# MCU.net
KiCad netlist of a schematic drawn in Altium Designer
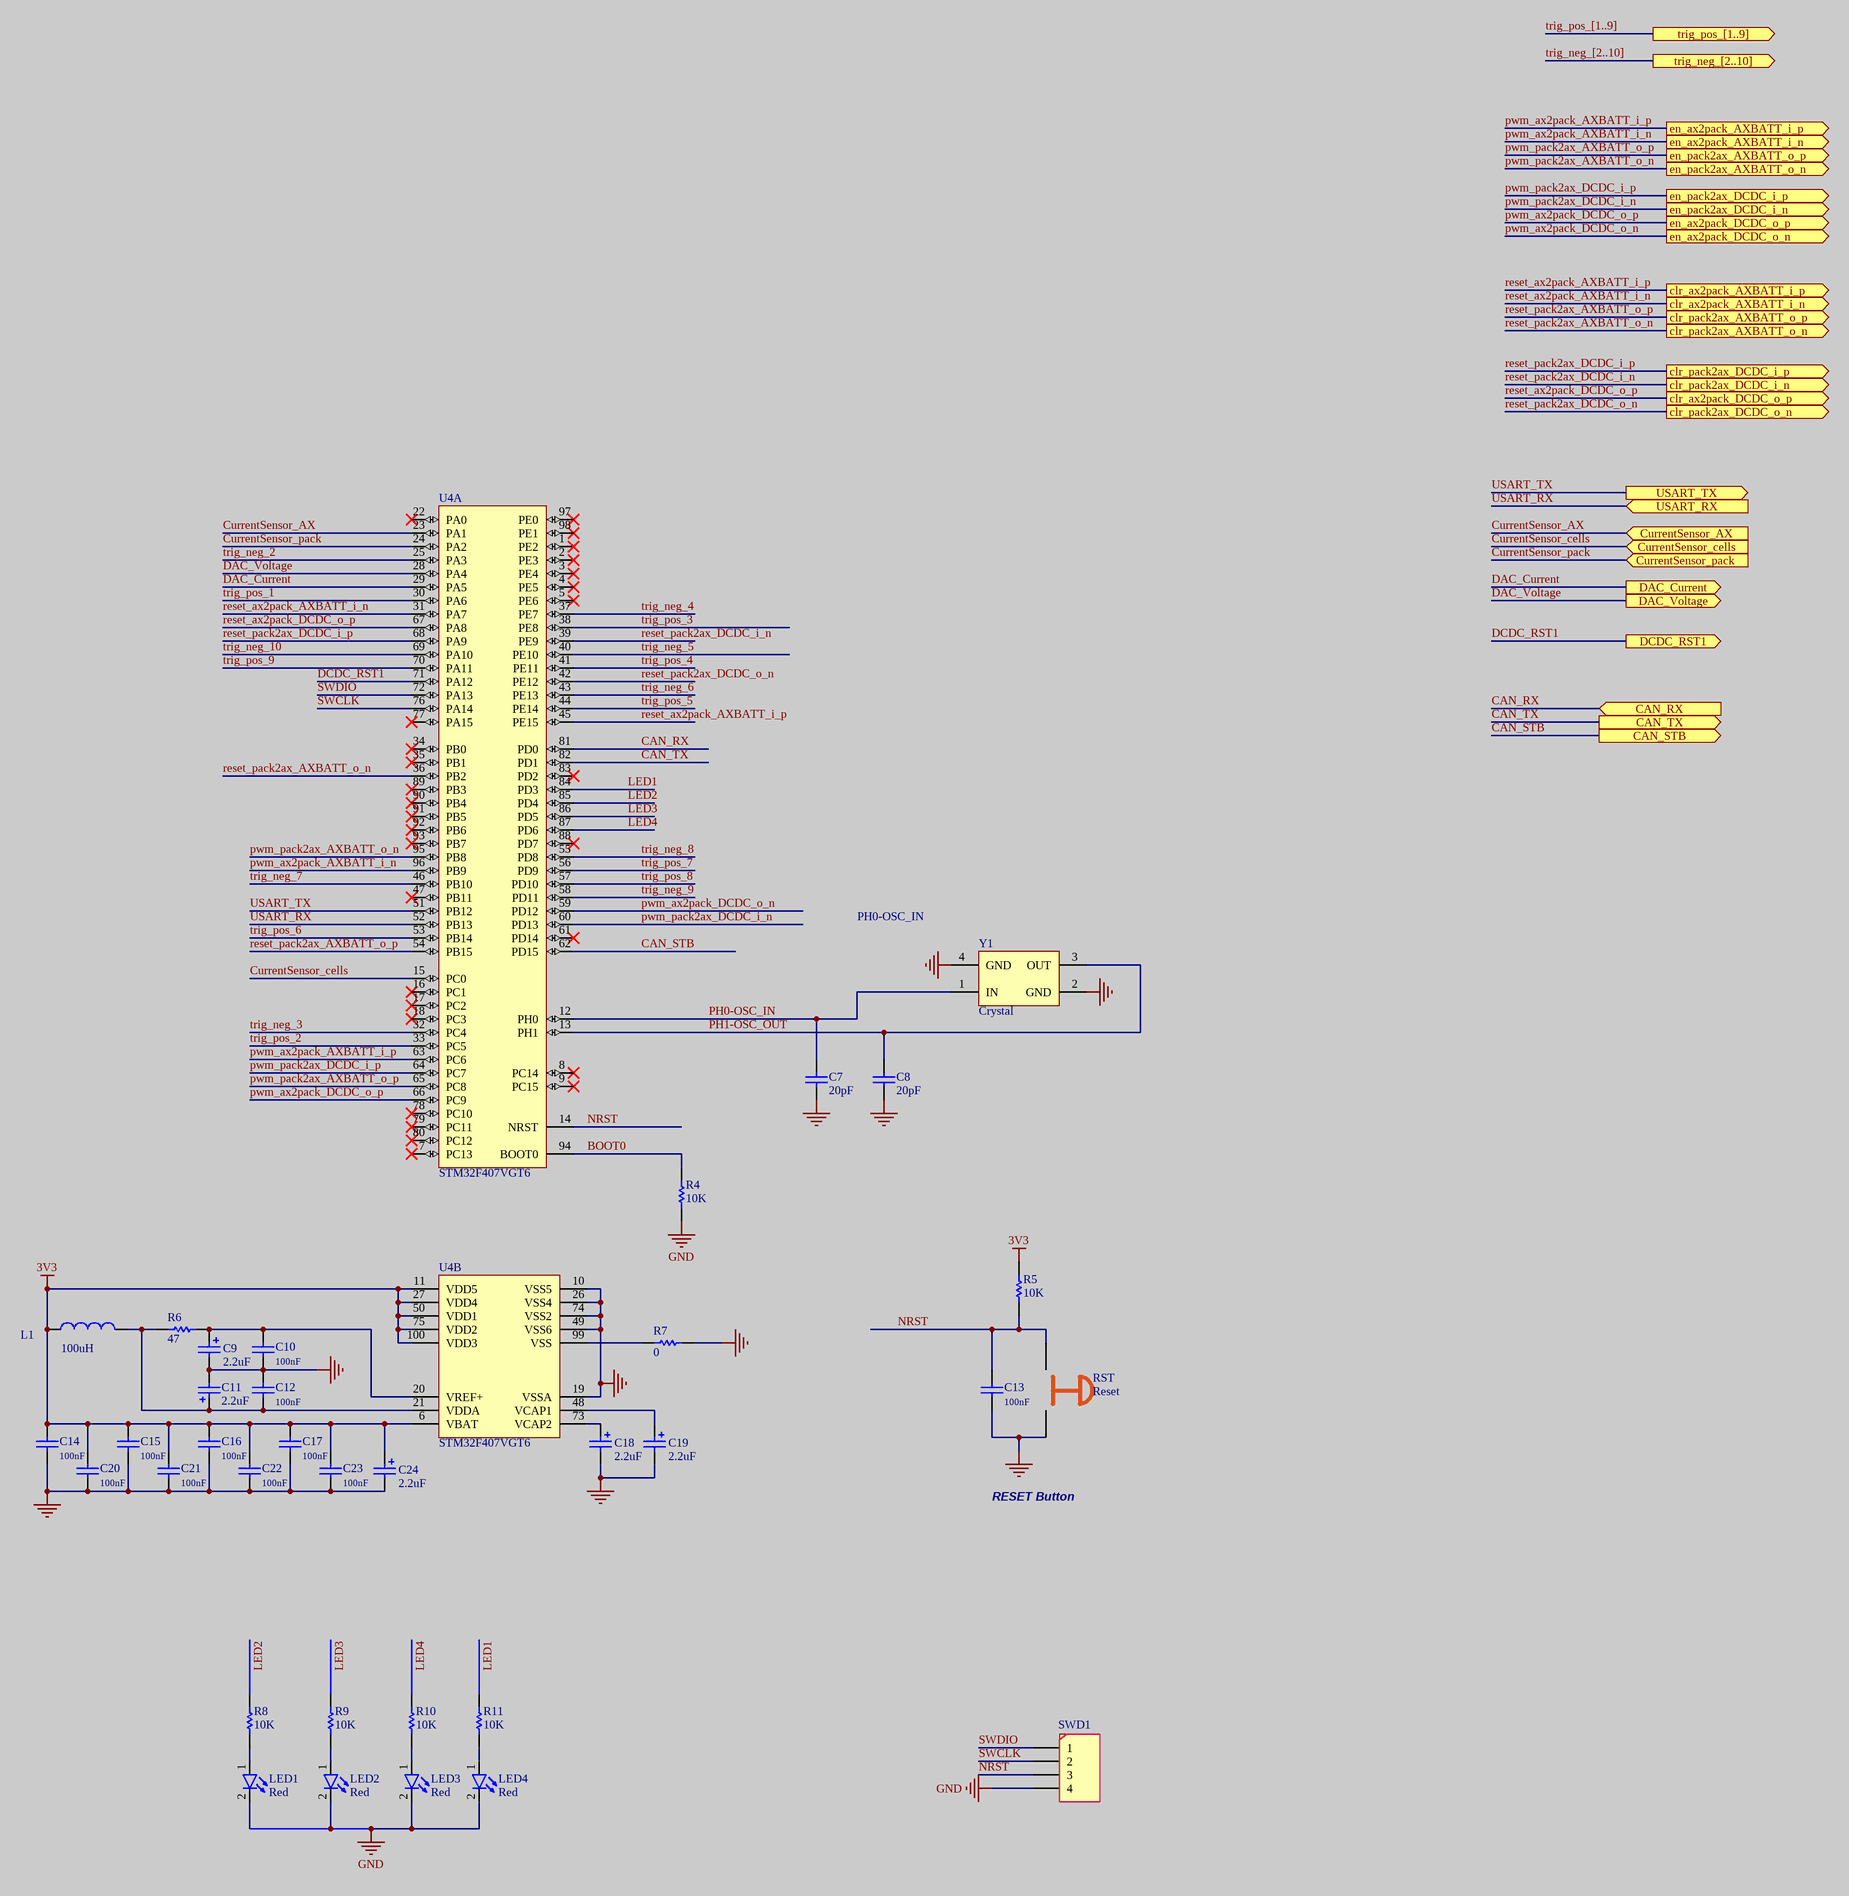
[diagram p0: MCU.SchDoc]

(export (version "E")
  (design (tool "Eeschema 10.0.6"))
  (components
    (comp (ref "C7")
      (value "20pF")
      (footprint "CAPC0603")
      (description "Capacitor")
      (fields (field (name "PUBLISHER") "Altium Limited"))
      (libsource (lib "eLIB") (part "Capacitor"))
    )
    (comp (ref "C8")
      (value "20pF")
      (footprint "CAPC0603")
      (description "Capacitor")
      (fields (field (name "PUBLISHER") "Altium Limited"))
      (libsource (lib "eLIB") (part "Capacitor"))
    )
    (comp (ref "C9")
      (value "2.2uF")
      (footprint "C1206")
      (description "Tantalium Capacitor Size C")
      (fields (field (name "PUBLISHER") "Altium Limited"))
      (libsource (lib "eLIB") (part "Cap_Tan"))
    )
    (comp (ref "C10")
      (value "100nF")
      (footprint "CAPC0603")
      (description "Capacitor")
      (fields (field (name "PUBLISHER") "Altium Limited"))
      (libsource (lib "eLIB") (part "Capacitor"))
    )
    (comp (ref "C11")
      (value "2.2uF")
      (footprint "C1206")
      (description "Tantalium Capacitor Size C")
      (fields (field (name "PUBLISHER") "Altium Limited"))
      (libsource (lib "eLIB") (part "Cap_Tan"))
    )
    (comp (ref "C12")
      (value "100nF")
      (footprint "CAPC0603")
      (description "Capacitor")
      (fields (field (name "PUBLISHER") "Altium Limited"))
      (libsource (lib "eLIB") (part "Capacitor"))
    )
    (comp (ref "C13")
      (value "100nF")
      (footprint "CAPC0603")
      (description "Capacitor")
      (fields (field (name "PUBLISHER") "Altium Limited"))
      (libsource (lib "eLIB") (part "Capacitor"))
    )
    (comp (ref "C14")
      (value "100nF")
      (footprint "CAPC0603")
      (description "Capacitor")
      (fields (field (name "PUBLISHER") "Altium Limited"))
      (libsource (lib "eLIB") (part "Capacitor"))
    )
    (comp (ref "C15")
      (value "100nF")
      (footprint "CAPC0603")
      (description "Capacitor")
      (fields (field (name "PUBLISHER") "Altium Limited"))
      (libsource (lib "eLIB") (part "Capacitor"))
    )
    (comp (ref "C16")
      (value "100nF")
      (footprint "CAPC0603")
      (description "Capacitor")
      (fields (field (name "PUBLISHER") "Altium Limited"))
      (libsource (lib "eLIB") (part "Capacitor"))
    )
    (comp (ref "C17")
      (value "100nF")
      (footprint "CAPC0603")
      (description "Capacitor")
      (fields (field (name "PUBLISHER") "Altium Limited"))
      (libsource (lib "eLIB") (part "Capacitor"))
    )
    (comp (ref "C18")
      (value "2.2uF")
      (footprint "C1206")
      (description "Tantalium Capacitor Size C")
      (fields (field (name "PUBLISHER") "Altium Limited"))
      (libsource (lib "eLIB") (part "Cap_Tan"))
    )
    (comp (ref "C19")
      (value "2.2uF")
      (footprint "C1206")
      (description "Tantalium Capacitor Size C")
      (fields (field (name "PUBLISHER") "Altium Limited"))
      (libsource (lib "eLIB") (part "Cap_Tan"))
    )
    (comp (ref "C20")
      (value "100nF")
      (footprint "CAPC0603")
      (description "Capacitor")
      (fields (field (name "PUBLISHER") "Altium Limited"))
      (libsource (lib "eLIB") (part "Capacitor"))
    )
    (comp (ref "C21")
      (value "100nF")
      (footprint "CAPC0603")
      (description "Capacitor")
      (fields (field (name "PUBLISHER") "Altium Limited"))
      (libsource (lib "eLIB") (part "Capacitor"))
    )
    (comp (ref "C22")
      (value "100nF")
      (footprint "CAPC0603")
      (description "Capacitor")
      (fields (field (name "PUBLISHER") "Altium Limited"))
      (libsource (lib "eLIB") (part "Capacitor"))
    )
    (comp (ref "C23")
      (value "100nF")
      (footprint "CAPC0603")
      (description "Capacitor")
      (fields (field (name "PUBLISHER") "Altium Limited"))
      (libsource (lib "eLIB") (part "Capacitor"))
    )
    (comp (ref "C24")
      (value "2.2uF")
      (footprint "C1206")
      (description "Tantalium Capacitor Size C")
      (fields (field (name "PUBLISHER") "Altium Limited"))
      (libsource (lib "eLIB") (part "Cap_Tan"))
    )
    (comp (ref "L1")
      (value "100uH")
      (footprint "RES1206")
      (fields (field (name "PUBLISHER") "Altium Limited"))
      (libsource (lib "eLIB") (part "INDUCTOR"))
    )
    (comp (ref "LED1")
      (value "Red")
      (footprint "LED")
      (description "LED")
      (fields (field (name "COLOR") "Red") (field (name "DESIGNER") "Saeid Jorablo"))
      (libsource (lib "TaraSchlib") (part "LED"))
    )
    (comp (ref "LED2")
      (value "Red")
      (footprint "LED")
      (description "LED")
      (fields (field (name "COLOR") "Red") (field (name "DESIGNER") "Saeid Jorablo"))
      (libsource (lib "TaraSchlib") (part "LED"))
    )
    (comp (ref "LED3")
      (value "Red")
      (footprint "LED")
      (description "LED")
      (fields (field (name "COLOR") "Red") (field (name "DESIGNER") "Saeid Jorablo"))
      (libsource (lib "TaraSchlib") (part "LED"))
    )
    (comp (ref "LED4")
      (value "Red")
      (footprint "LED")
      (description "LED")
      (fields (field (name "COLOR") "Red") (field (name "DESIGNER") "Saeid Jorablo"))
      (libsource (lib "TaraSchlib") (part "LED"))
    )
    (comp (ref "R4")
      (value "10K")
      (footprint "RESC0603")
      (description "0603,0.1W")
      (fields (field (name "PUBLISHER") "Altium Limited"))
      (libsource (lib "eLIB") (part "Resistor"))
    )
    (comp (ref "R5")
      (value "10K")
      (footprint "RESC0603")
      (description "0603,0.1W")
      (fields (field (name "PUBLISHER") "Altium Limited"))
      (libsource (lib "eLIB") (part "Resistor"))
    )
    (comp (ref "R6")
      (value "47")
      (footprint "RESC0603")
      (description "0603,0.1W")
      (fields (field (name "PUBLISHER") "Altium Limited"))
      (libsource (lib "eLIB") (part "Resistor"))
    )
    (comp (ref "R7")
      (value "0")
      (footprint "RESC0603")
      (description "0603,0.1W")
      (fields (field (name "PUBLISHER") "Altium Limited"))
      (libsource (lib "eLIB") (part "Resistor"))
    )
    (comp (ref "R8")
      (value "10K")
      (footprint "RESC0603")
      (description "0603,0.1W")
      (fields (field (name "PUBLISHER") "Altium Limited"))
      (libsource (lib "eLIB") (part "Resistor"))
    )
    (comp (ref "R9")
      (value "10K")
      (footprint "RESC0603")
      (description "0603,0.1W")
      (fields (field (name "PUBLISHER") "Altium Limited"))
      (libsource (lib "eLIB") (part "Resistor"))
    )
    (comp (ref "R10")
      (value "10K")
      (footprint "RESC0603")
      (description "0603,0.1W")
      (fields (field (name "PUBLISHER") "Altium Limited"))
      (libsource (lib "eLIB") (part "Resistor"))
    )
    (comp (ref "R11")
      (value "10K")
      (footprint "RESC0603")
      (description "0603,0.1W")
      (fields (field (name "PUBLISHER") "Altium Limited"))
      (libsource (lib "eLIB") (part "Resistor"))
    )
    (comp (ref "RST")
      (value "Reset")
      (footprint "SWITCH-PB4")
      (description "4-Pin Push Button")
      (libsource (lib "eLIB") (part "Swtich-PB4"))
    )
    (comp (ref "SWD1")
      (value "~")
      (footprint "HEADER1*4")
      (description "Header, 4-Pin")
      (libsource (lib "eLIB") (part "Header1*4"))
    )
    (comp (ref "U4")
      (value "STM32F407VGT6")
      (footprint "QFP50P1600X1600X160-100N")
      (description "STM32 Manta (STM32F407VGT6)")
      (libsource (lib "eLIB") (part "STM32H743"))
    )
    (comp (ref "Y1")
      (value "Crystal")
      (footprint "eLIB:ABM3B-8.000MHZ-B2")
      (description "ABM3B-8.000MHZ-B2")
      (libsource (lib "eLIB") (part "Crystal"))
    )
  )
  (nets
    (net (code "1") (name "/BOOT0") (class "Default")
      (node (ref "R4") (pin "2") (pinfunction "2_2") (pintype "passive"))
      (node (ref "U4") (pin "94") (pinfunction "BOOT0_94") (pintype "open_collector"))
    )
    (net (code "2") (name "/CAN_RX") (class "Default")
      (node (ref "U4") (pin "81") (pinfunction "PD0_81") (pintype "bidirectional"))
    )
    (net (code "3") (name "/CAN_STB") (class "Default")
      (node (ref "U4") (pin "62") (pinfunction "PD15_62") (pintype "bidirectional"))
    )
    (net (code "4") (name "/CAN_TX") (class "Default")
      (node (ref "U4") (pin "82") (pinfunction "PD1_82") (pintype "bidirectional"))
    )
    (net (code "5") (name "/CurrentSensor_AX") (class "Default")
      (node (ref "U4") (pin "23") (pinfunction "PA1_23") (pintype "bidirectional"))
    )
    (net (code "6") (name "/CurrentSensor_cells") (class "Default")
      (node (ref "U4") (pin "15") (pinfunction "PC0_15") (pintype "bidirectional"))
    )
    (net (code "7") (name "/CurrentSensor_pack") (class "Default")
      (node (ref "U4") (pin "24") (pinfunction "PA2_24") (pintype "bidirectional"))
    )
    (net (code "8") (name "/DAC_Current") (class "Default")
      (node (ref "U4") (pin "29") (pinfunction "PA5_29") (pintype "bidirectional"))
    )
    (net (code "9") (name "/DAC_Voltage") (class "Default")
      (node (ref "U4") (pin "28") (pinfunction "PA4_28") (pintype "bidirectional"))
    )
    (net (code "10") (name "/DCDC_RST1") (class "Default")
      (node (ref "U4") (pin "71") (pinfunction "PA12_71") (pintype "bidirectional"))
    )
    (net (code "11") (name "/LED1") (class "Default")
      (node (ref "R11") (pin "2") (pinfunction "2_2") (pintype "passive"))
      (node (ref "U4") (pin "84") (pinfunction "PD3_84") (pintype "bidirectional"))
    )
    (net (code "12") (name "/LED2") (class "Default")
      (node (ref "R8") (pin "2") (pinfunction "2_2") (pintype "passive"))
      (node (ref "U4") (pin "85") (pinfunction "PD4_85") (pintype "bidirectional"))
    )
    (net (code "13") (name "/LED3") (class "Default")
      (node (ref "R9") (pin "2") (pinfunction "2_2") (pintype "passive"))
      (node (ref "U4") (pin "86") (pinfunction "PD5_86") (pintype "bidirectional"))
    )
    (net (code "14") (name "/LED4") (class "Default")
      (node (ref "R10") (pin "2") (pinfunction "2_2") (pintype "passive"))
      (node (ref "U4") (pin "87") (pinfunction "PD6_87") (pintype "bidirectional"))
    )
    (net (code "15") (name "/NRST") (class "Default")
      (node (ref "C13") (pin "1") (pinfunction "1_1") (pintype "passive"))
      (node (ref "R5") (pin "1") (pinfunction "1_1") (pintype "passive"))
      (node (ref "RST") (pin "1") (pinfunction "1_1") (pintype "passive"))
      (node (ref "SWD1") (pin "3") (pinfunction "3_3") (pintype "passive"))
      (node (ref "U4") (pin "14") (pinfunction "NRST_14") (pintype "passive"))
    )
    (net (code "16") (name "/PH0-OSC_IN") (class "Default")
      (node (ref "C7") (pin "2") (pinfunction "2_2") (pintype "passive"))
      (node (ref "U4") (pin "12") (pinfunction "PH0_12") (pintype "bidirectional"))
      (node (ref "Y1") (pin "1") (pinfunction "IN_1") (pintype "passive"))
    )
    (net (code "17") (name "/PH1-OSC_OUT") (class "Default")
      (node (ref "C8") (pin "2") (pinfunction "2_2") (pintype "passive"))
      (node (ref "U4") (pin "13") (pinfunction "PH1_13") (pintype "bidirectional"))
      (node (ref "Y1") (pin "3") (pinfunction "OUT_3") (pintype "passive"))
    )
    (net (code "18") (name "/SWCLK") (class "Default")
      (node (ref "SWD1") (pin "2") (pinfunction "2_2") (pintype "passive"))
      (node (ref "U4") (pin "76") (pinfunction "PA14_76") (pintype "bidirectional"))
    )
    (net (code "19") (name "/SWDIO") (class "Default")
      (node (ref "SWD1") (pin "1") (pinfunction "1_1") (pintype "passive"))
      (node (ref "U4") (pin "72") (pinfunction "PA13_72") (pintype "bidirectional"))
    )
    (net (code "20") (name "/USART_RX") (class "Default")
      (node (ref "U4") (pin "52") (pinfunction "PB13_52") (pintype "bidirectional"))
    )
    (net (code "21") (name "/USART_TX") (class "Default")
      (node (ref "U4") (pin "51") (pinfunction "PB12_51") (pintype "bidirectional"))
    )
    (net (code "22") (name "/pwm_ax2pack_AXBATT_i_n") (class "Default")
      (node (ref "U4") (pin "96") (pinfunction "PB9_96") (pintype "bidirectional"))
    )
    (net (code "23") (name "/pwm_ax2pack_AXBATT_i_p") (class "Default")
      (node (ref "U4") (pin "63") (pinfunction "PC6_63") (pintype "bidirectional"))
    )
    (net (code "24") (name "/pwm_ax2pack_DCDC_o_n") (class "Default")
      (node (ref "U4") (pin "59") (pinfunction "PD12_59") (pintype "bidirectional"))
    )
    (net (code "25") (name "/pwm_ax2pack_DCDC_o_p") (class "Default")
      (node (ref "U4") (pin "66") (pinfunction "PC9_66") (pintype "bidirectional"))
    )
    (net (code "26") (name "/pwm_pack2ax_AXBATT_o_n") (class "Default")
      (node (ref "U4") (pin "95") (pinfunction "PB8_95") (pintype "bidirectional"))
    )
    (net (code "27") (name "/pwm_pack2ax_AXBATT_o_p") (class "Default")
      (node (ref "U4") (pin "65") (pinfunction "PC8_65") (pintype "bidirectional"))
    )
    (net (code "28") (name "/pwm_pack2ax_DCDC_i_n") (class "Default")
      (node (ref "U4") (pin "60") (pinfunction "PD13_60") (pintype "bidirectional"))
    )
    (net (code "29") (name "/pwm_pack2ax_DCDC_i_p") (class "Default")
      (node (ref "U4") (pin "64") (pinfunction "PC7_64") (pintype "bidirectional"))
    )
    (net (code "30") (name "/reset_ax2pack_AXBATT_i_n") (class "Default")
      (node (ref "U4") (pin "31") (pinfunction "PA7_31") (pintype "bidirectional"))
    )
    (net (code "31") (name "/reset_ax2pack_AXBATT_i_p") (class "Default")
      (node (ref "U4") (pin "45") (pinfunction "PE15_45") (pintype "bidirectional"))
    )
    (net (code "32") (name "/reset_ax2pack_DCDC_o_p") (class "Default")
      (node (ref "U4") (pin "67") (pinfunction "PA8_67") (pintype "bidirectional"))
    )
    (net (code "33") (name "/reset_pack2ax_AXBATT_o_n") (class "Default")
      (node (ref "U4") (pin "36") (pinfunction "PB2_36") (pintype "bidirectional"))
    )
    (net (code "34") (name "/reset_pack2ax_AXBATT_o_p") (class "Default")
      (node (ref "U4") (pin "54") (pinfunction "PB15_54") (pintype "bidirectional"))
    )
    (net (code "35") (name "/reset_pack2ax_DCDC_i_n") (class "Default")
      (node (ref "U4") (pin "39") (pinfunction "PE9_39") (pintype "bidirectional"))
    )
    (net (code "36") (name "/reset_pack2ax_DCDC_i_p") (class "Default")
      (node (ref "U4") (pin "68") (pinfunction "PA9_68") (pintype "bidirectional"))
    )
    (net (code "37") (name "/reset_pack2ax_DCDC_o_n") (class "Default")
      (node (ref "U4") (pin "42") (pinfunction "PE12_42") (pintype "bidirectional"))
    )
    (net (code "38") (name "/trig_neg_2") (class "Default")
      (node (ref "U4") (pin "25") (pinfunction "PA3_25") (pintype "bidirectional"))
    )
    (net (code "39") (name "/trig_neg_3") (class "Default")
      (node (ref "U4") (pin "32") (pinfunction "PC4_32") (pintype "bidirectional"))
    )
    (net (code "40") (name "/trig_neg_4") (class "Default")
      (node (ref "U4") (pin "37") (pinfunction "PE7_37") (pintype "bidirectional"))
    )
    (net (code "41") (name "/trig_neg_5") (class "Default")
      (node (ref "U4") (pin "40") (pinfunction "PE10_40") (pintype "bidirectional"))
    )
    (net (code "42") (name "/trig_neg_6") (class "Default")
      (node (ref "U4") (pin "43") (pinfunction "PE13_43") (pintype "bidirectional"))
    )
    (net (code "43") (name "/trig_neg_7") (class "Default")
      (node (ref "U4") (pin "46") (pinfunction "PB10_46") (pintype "bidirectional"))
    )
    (net (code "44") (name "/trig_neg_8") (class "Default")
      (node (ref "U4") (pin "55") (pinfunction "PD8_55") (pintype "bidirectional"))
    )
    (net (code "45") (name "/trig_neg_9") (class "Default")
      (node (ref "U4") (pin "58") (pinfunction "PD11_58") (pintype "bidirectional"))
    )
    (net (code "46") (name "/trig_neg_10") (class "Default")
      (node (ref "U4") (pin "69") (pinfunction "PA10_69") (pintype "bidirectional"))
    )
    (net (code "48") (name "/trig_pos_1") (class "Default")
      (node (ref "U4") (pin "30") (pinfunction "PA6_30") (pintype "bidirectional"))
    )
    (net (code "49") (name "/trig_pos_2") (class "Default")
      (node (ref "U4") (pin "33") (pinfunction "PC5_33") (pintype "bidirectional"))
    )
    (net (code "50") (name "/trig_pos_3") (class "Default")
      (node (ref "U4") (pin "38") (pinfunction "PE8_38") (pintype "bidirectional"))
    )
    (net (code "51") (name "/trig_pos_4") (class "Default")
      (node (ref "U4") (pin "41") (pinfunction "PE11_41") (pintype "bidirectional"))
    )
    (net (code "52") (name "/trig_pos_5") (class "Default")
      (node (ref "U4") (pin "44") (pinfunction "PE14_44") (pintype "bidirectional"))
    )
    (net (code "53") (name "/trig_pos_6") (class "Default")
      (node (ref "U4") (pin "53") (pinfunction "PB14_53") (pintype "bidirectional"))
    )
    (net (code "54") (name "/trig_pos_7") (class "Default")
      (node (ref "U4") (pin "56") (pinfunction "PD9_56") (pintype "bidirectional"))
    )
    (net (code "55") (name "/trig_pos_8") (class "Default")
      (node (ref "U4") (pin "57") (pinfunction "PD10_57") (pintype "bidirectional"))
    )
    (net (code "56") (name "/trig_pos_9") (class "Default")
      (node (ref "U4") (pin "70") (pinfunction "PA11_70") (pintype "bidirectional"))
    )
    (net (code "58") (name "3V3") (class "Default")
      (node (ref "C14") (pin "1") (pinfunction "1_1") (pintype "passive"))
      (node (ref "C15") (pin "1") (pinfunction "1_1") (pintype "passive"))
      (node (ref "C16") (pin "1") (pinfunction "1_1") (pintype "passive"))
      (node (ref "C17") (pin "1") (pinfunction "1_1") (pintype "passive"))
      (node (ref "C20") (pin "1") (pinfunction "1_1") (pintype "passive"))
      (node (ref "C21") (pin "1") (pinfunction "1_1") (pintype "passive"))
      (node (ref "C22") (pin "1") (pinfunction "1_1") (pintype "passive"))
      (node (ref "C23") (pin "1") (pinfunction "1_1") (pintype "passive"))
      (node (ref "C24") (pin "1") (pinfunction "1_1") (pintype "passive"))
      (node (ref "L1") (pin "1") (pinfunction "1_1") (pintype "passive"))
      (node (ref "R5") (pin "2") (pinfunction "2_2") (pintype "passive"))
      (node (ref "U4") (pin "100") (pinfunction "VDD3_100") (pintype "passive"))
      (node (ref "U4") (pin "11") (pinfunction "VDD5_11") (pintype "passive"))
      (node (ref "U4") (pin "27") (pinfunction "VDD4_27") (pintype "passive"))
      (node (ref "U4") (pin "50") (pinfunction "VDD1_50") (pintype "passive"))
      (node (ref "U4") (pin "6") (pinfunction "VBAT_6") (pintype "passive"))
      (node (ref "U4") (pin "75") (pinfunction "VDD2_75") (pintype "passive"))
    )
    (net (code "59") (name "GND") (class "Default")
      (node (ref "C10") (pin "2") (pinfunction "2_2") (pintype "passive"))
      (node (ref "C11") (pin "2") (pinfunction "2_2") (pintype "passive"))
      (node (ref "C12") (pin "1") (pinfunction "1_1") (pintype "passive"))
      (node (ref "C13") (pin "2") (pinfunction "2_2") (pintype "passive"))
      (node (ref "C14") (pin "2") (pinfunction "2_2") (pintype "passive"))
      (node (ref "C15") (pin "2") (pinfunction "2_2") (pintype "passive"))
      (node (ref "C16") (pin "2") (pinfunction "2_2") (pintype "passive"))
      (node (ref "C17") (pin "2") (pinfunction "2_2") (pintype "passive"))
      (node (ref "C18") (pin "2") (pinfunction "2_2") (pintype "passive"))
      (node (ref "C19") (pin "2") (pinfunction "2_2") (pintype "passive"))
      (node (ref "C20") (pin "2") (pinfunction "2_2") (pintype "passive"))
      (node (ref "C21") (pin "2") (pinfunction "2_2") (pintype "passive"))
      (node (ref "C22") (pin "2") (pinfunction "2_2") (pintype "passive"))
      (node (ref "C23") (pin "2") (pinfunction "2_2") (pintype "passive"))
      (node (ref "C24") (pin "2") (pinfunction "2_2") (pintype "passive"))
      (node (ref "C7") (pin "1") (pinfunction "1_1") (pintype "passive"))
      (node (ref "C8") (pin "1") (pinfunction "1_1") (pintype "passive"))
      (node (ref "C9") (pin "2") (pinfunction "2_2") (pintype "passive"))
      (node (ref "LED1") (pin "2") (pinfunction "K_2") (pintype "passive"))
      (node (ref "LED2") (pin "2") (pinfunction "K_2") (pintype "passive"))
      (node (ref "LED3") (pin "2") (pinfunction "K_2") (pintype "passive"))
      (node (ref "LED4") (pin "2") (pinfunction "K_2") (pintype "passive"))
      (node (ref "R4") (pin "1") (pinfunction "1_1") (pintype "passive"))
      (node (ref "R7") (pin "1") (pinfunction "1_1") (pintype "passive"))
      (node (ref "RST") (pin "2") (pinfunction "2_2") (pintype "passive"))
      (node (ref "SWD1") (pin "4") (pinfunction "4_4") (pintype "passive"))
      (node (ref "U4") (pin "10") (pinfunction "VSS5_10") (pintype "passive"))
      (node (ref "U4") (pin "19") (pinfunction "VSSA_19") (pintype "passive"))
      (node (ref "U4") (pin "26") (pinfunction "VSS4_26") (pintype "passive"))
      (node (ref "U4") (pin "49") (pinfunction "VSS6_49") (pintype "passive"))
      (node (ref "U4") (pin "74") (pinfunction "VSS2_74") (pintype "passive"))
      (node (ref "Y1") (pin "2") (pinfunction "GND_2") (pintype "passive"))
      (node (ref "Y1") (pin "4") (pinfunction "GND_4") (pintype "passive"))
    )
    (net (code "60") (name "Net-(LED1-A)") (class "Default")
      (node (ref "LED1") (pin "1") (pinfunction "A_1") (pintype "passive"))
      (node (ref "R8") (pin "1") (pinfunction "1_1") (pintype "passive"))
    )
    (net (code "61") (name "Net-(LED2-A)") (class "Default")
      (node (ref "LED2") (pin "1") (pinfunction "A_1") (pintype "passive"))
      (node (ref "R9") (pin "1") (pinfunction "1_1") (pintype "passive"))
    )
    (net (code "62") (name "Net-(LED3-A)") (class "Default")
      (node (ref "LED3") (pin "1") (pinfunction "A_1") (pintype "passive"))
      (node (ref "R10") (pin "1") (pinfunction "1_1") (pintype "passive"))
    )
    (net (code "63") (name "Net-(LED4-A)") (class "Default")
      (node (ref "LED4") (pin "1") (pinfunction "A_1") (pintype "passive"))
      (node (ref "R11") (pin "1") (pinfunction "1_1") (pintype "passive"))
    )
    (net (code "64") (name "Net-(U4B-VCAP1)") (class "Default")
      (node (ref "C19") (pin "1") (pinfunction "1_1") (pintype "passive"))
      (node (ref "U4") (pin "48") (pinfunction "VCAP1_48") (pintype "passive"))
    )
    (net (code "65") (name "Net-(U4B-VCAP2)") (class "Default")
      (node (ref "C18") (pin "1") (pinfunction "1_1") (pintype "passive"))
      (node (ref "U4") (pin "73") (pinfunction "VCAP2_73") (pintype "passive"))
    )
    (net (code "66") (name "Net-(U4B-VDDA)") (class "Default")
      (node (ref "C11") (pin "1") (pinfunction "1_1") (pintype "passive"))
      (node (ref "C12") (pin "2") (pinfunction "2_2") (pintype "passive"))
      (node (ref "L1") (pin "2") (pinfunction "2_2") (pintype "passive"))
      (node (ref "R6") (pin "2") (pinfunction "2_2") (pintype "passive"))
      (node (ref "U4") (pin "21") (pinfunction "VDDA_21") (pintype "passive"))
    )
    (net (code "67") (name "Net-(U4B-VREF+)") (class "Default")
      (node (ref "C10") (pin "1") (pinfunction "1_1") (pintype "passive"))
      (node (ref "C9") (pin "1") (pinfunction "1_1") (pintype "passive"))
      (node (ref "R6") (pin "1") (pinfunction "1_1") (pintype "passive"))
      (node (ref "U4") (pin "20") (pinfunction "VREF+_20") (pintype "passive"))
    )
    (net (code "68") (name "Net-(U4B-VSS)") (class "Default")
      (node (ref "R7") (pin "2") (pinfunction "2_2") (pintype "passive"))
      (node (ref "U4") (pin "99") (pinfunction "VSS_99") (pintype "passive"))
    )
    (net (code "69") (name "unconnected-(U4A-PA0-Pad22)") (class "Default")
      (node (ref "U4") (pin "22") (pinfunction "PA0_22") (pintype "bidirectional+no_connect"))
    )
    (net (code "70") (name "unconnected-(U4A-PA15-Pad77)") (class "Default")
      (node (ref "U4") (pin "77") (pinfunction "PA15_77") (pintype "bidirectional+no_connect"))
    )
    (net (code "71") (name "unconnected-(U4A-PB0-Pad34)") (class "Default")
      (node (ref "U4") (pin "34") (pinfunction "PB0_34") (pintype "bidirectional+no_connect"))
    )
    (net (code "72") (name "unconnected-(U4A-PB1-Pad35)") (class "Default")
      (node (ref "U4") (pin "35") (pinfunction "PB1_35") (pintype "bidirectional+no_connect"))
    )
    (net (code "73") (name "unconnected-(U4A-PB3-Pad89)") (class "Default")
      (node (ref "U4") (pin "89") (pinfunction "PB3_89") (pintype "bidirectional+no_connect"))
    )
    (net (code "74") (name "unconnected-(U4A-PB4-Pad90)") (class "Default")
      (node (ref "U4") (pin "90") (pinfunction "PB4_90") (pintype "bidirectional+no_connect"))
    )
    (net (code "75") (name "unconnected-(U4A-PB5-Pad91)") (class "Default")
      (node (ref "U4") (pin "91") (pinfunction "PB5_91") (pintype "bidirectional+no_connect"))
    )
    (net (code "76") (name "unconnected-(U4A-PB6-Pad92)") (class "Default")
      (node (ref "U4") (pin "92") (pinfunction "PB6_92") (pintype "bidirectional+no_connect"))
    )
    (net (code "77") (name "unconnected-(U4A-PB7-Pad93)") (class "Default")
      (node (ref "U4") (pin "93") (pinfunction "PB7_93") (pintype "bidirectional+no_connect"))
    )
    (net (code "78") (name "unconnected-(U4A-PB11-Pad47)") (class "Default")
      (node (ref "U4") (pin "47") (pinfunction "PB11_47") (pintype "bidirectional+no_connect"))
    )
    (net (code "79") (name "unconnected-(U4A-PC1-Pad16)") (class "Default")
      (node (ref "U4") (pin "16") (pinfunction "PC1_16") (pintype "bidirectional+no_connect"))
    )
    (net (code "80") (name "unconnected-(U4A-PC2-Pad17)") (class "Default")
      (node (ref "U4") (pin "17") (pinfunction "PC2_17") (pintype "bidirectional+no_connect"))
    )
    (net (code "81") (name "unconnected-(U4A-PC3-Pad18)") (class "Default")
      (node (ref "U4") (pin "18") (pinfunction "PC3_18") (pintype "bidirectional+no_connect"))
    )
    (net (code "82") (name "unconnected-(U4A-PC10-Pad78)") (class "Default")
      (node (ref "U4") (pin "78") (pinfunction "PC10_78") (pintype "bidirectional+no_connect"))
    )
    (net (code "83") (name "unconnected-(U4A-PC11-Pad79)") (class "Default")
      (node (ref "U4") (pin "79") (pinfunction "PC11_79") (pintype "bidirectional+no_connect"))
    )
    (net (code "84") (name "unconnected-(U4A-PC12-Pad80)") (class "Default")
      (node (ref "U4") (pin "80") (pinfunction "PC12_80") (pintype "bidirectional+no_connect"))
    )
    (net (code "85") (name "unconnected-(U4A-PC13-Pad7)") (class "Default")
      (node (ref "U4") (pin "7") (pinfunction "PC13_7") (pintype "bidirectional+no_connect"))
    )
    (net (code "86") (name "unconnected-(U4A-PC14-Pad8)") (class "Default")
      (node (ref "U4") (pin "8") (pinfunction "PC14_8") (pintype "bidirectional+no_connect"))
    )
    (net (code "87") (name "unconnected-(U4A-PC15-Pad9)") (class "Default")
      (node (ref "U4") (pin "9") (pinfunction "PC15_9") (pintype "bidirectional+no_connect"))
    )
    (net (code "88") (name "unconnected-(U4A-PD2-Pad83)") (class "Default")
      (node (ref "U4") (pin "83") (pinfunction "PD2_83") (pintype "bidirectional+no_connect"))
    )
    (net (code "89") (name "unconnected-(U4A-PD7-Pad88)") (class "Default")
      (node (ref "U4") (pin "88") (pinfunction "PD7_88") (pintype "bidirectional+no_connect"))
    )
    (net (code "90") (name "unconnected-(U4A-PD14-Pad61)") (class "Default")
      (node (ref "U4") (pin "61") (pinfunction "PD14_61") (pintype "bidirectional+no_connect"))
    )
    (net (code "91") (name "unconnected-(U4A-PE0-Pad97)") (class "Default")
      (node (ref "U4") (pin "97") (pinfunction "PE0_97") (pintype "bidirectional+no_connect"))
    )
    (net (code "92") (name "unconnected-(U4A-PE1-Pad98)") (class "Default")
      (node (ref "U4") (pin "98") (pinfunction "PE1_98") (pintype "bidirectional+no_connect"))
    )
    (net (code "93") (name "unconnected-(U4A-PE2-Pad1)") (class "Default")
      (node (ref "U4") (pin "1") (pinfunction "PE2_1") (pintype "bidirectional+no_connect"))
    )
    (net (code "94") (name "unconnected-(U4A-PE3-Pad2)") (class "Default")
      (node (ref "U4") (pin "2") (pinfunction "PE3_2") (pintype "bidirectional+no_connect"))
    )
    (net (code "95") (name "unconnected-(U4A-PE4-Pad3)") (class "Default")
      (node (ref "U4") (pin "3") (pinfunction "PE4_3") (pintype "bidirectional+no_connect"))
    )
    (net (code "96") (name "unconnected-(U4A-PE5-Pad4)") (class "Default")
      (node (ref "U4") (pin "4") (pinfunction "PE5_4") (pintype "bidirectional+no_connect"))
    )
    (net (code "97") (name "unconnected-(U4A-PE6-Pad5)") (class "Default")
      (node (ref "U4") (pin "5") (pinfunction "PE6_5") (pintype "bidirectional+no_connect"))
    )
  )
)
